# NinjaPCRf-131101.net
KiCad netlist of a schematic drawn in EAGLE
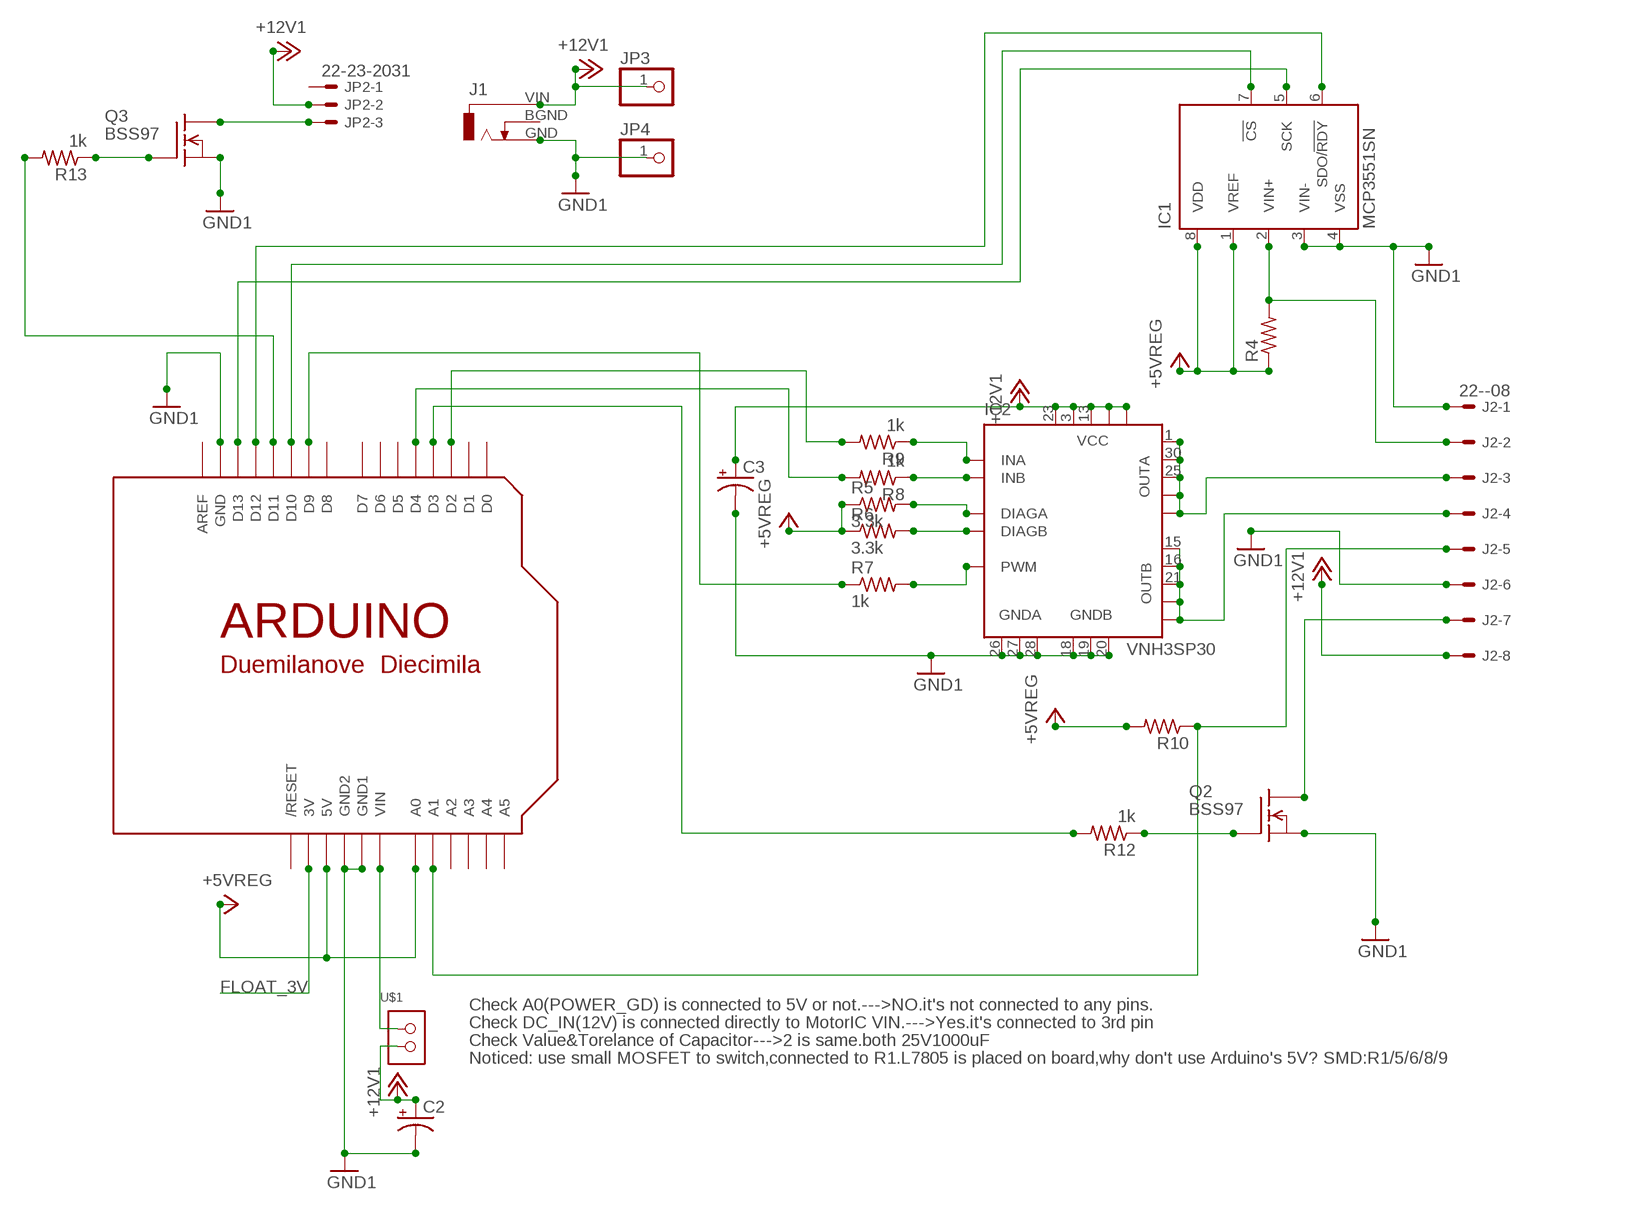
[diagram p0: schematic, sheet 1]

(export (version "E")
  (design (tool "Eeschema 10.0.6"))
  (components
    (comp (ref "C2")
      (value "CPOL-USE5-8.5")
      (footprint "eagle-import:E5-8,5")
      (libsource (lib "eagle-import") (part "CPOL-USE5-8.5"))
    )
    (comp (ref "C3")
      (value "CPOL-USE5-13")
      (footprint "eagle-import:E5-13")
      (libsource (lib "eagle-import") (part "CPOL-USE5-13"))
    )
    (comp (ref "IC1")
      (value "MCP3551SN")
      (footprint "eagle-import:SO-08")
      (fields (field (name "MPN") "MCP3551-E/SN"))
      (libsource (lib "eagle-import") (part "MCP355SN1"))
    )
    (comp (ref "IC2")
      (value "VNH3SP30")
      (footprint "eagle-import:MULTIPOWERSO-30")
      (fields (field (name "MPN") "VNH3SP30-E"))
      (libsource (lib "eagle-import") (part "VNH3SP30"))
    )
    (comp (ref "J1")
      (value "DCJ0303")
      (footprint "eagle-import:DCJ0303")
      (libsource (lib "eagle-import") (part "DCJ0303"))
    )
    (comp (ref "J2")
      (value "22--08")
      (footprint "eagle-import:POLOLU-8-VERTICAL")
      (libsource (lib "eagle-import") (part "22-?-08"))
    )
    (comp (ref "JP2")
      (value "22-23-2031")
      (footprint "eagle-import:22-23-2031")
      (fields (field (name "MF") "MOLEX"))
      (libsource (lib "eagle-import") (part "22-23-2031"))
    )
    (comp (ref "JP3")
      (value "PINHD-1X1")
      (footprint "eagle-import:1X01")
      (libsource (lib "eagle-import") (part "PINHD-1X1"))
    )
    (comp (ref "JP4")
      (value "PINHD-1X1")
      (footprint "eagle-import:1X01")
      (libsource (lib "eagle-import") (part "PINHD-1X1"))
    )
    (comp (ref "Q2")
      (value "BSS97")
      (footprint "eagle-import:TO202")
      (libsource (lib "eagle-import") (part "BSS97"))
    )
    (comp (ref "Q3")
      (value "BSS97")
      (footprint "eagle-import:TO202")
      (libsource (lib "eagle-import") (part "BSS97"))
    )
    (comp (ref "R4")
      (value "R-US_R0603")
      (footprint "eagle-import:R0603")
      (libsource (lib "eagle-import") (part "resistor_R-US_R0603"))
    )
    (comp (ref "R5")
      (value "3.3k")
      (footprint "eagle-import:R0603")
      (libsource (lib "eagle-import") (part "R-US_R0603"))
    )
    (comp (ref "R6")
      (value "3.3k")
      (footprint "eagle-import:R0603")
      (libsource (lib "eagle-import") (part "R-US_R0603"))
    )
    (comp (ref "R7")
      (value "1k")
      (footprint "eagle-import:R0603")
      (libsource (lib "eagle-import") (part "R-US_R0603"))
    )
    (comp (ref "R8")
      (value "1k")
      (footprint "eagle-import:R0603")
      (libsource (lib "eagle-import") (part "R-US_R0603"))
    )
    (comp (ref "R9")
      (value "1k")
      (footprint "eagle-import:R0603")
      (libsource (lib "eagle-import") (part "R-US_R0603"))
    )
    (comp (ref "R10")
      (value "R-US_R0603")
      (footprint "eagle-import:R0603")
      (libsource (lib "eagle-import") (part "resistor_R-US_R0603"))
    )
    (comp (ref "R12")
      (value "1k")
      (footprint "eagle-import:R0603")
      (libsource (lib "eagle-import") (part "resistor_R-US_R0603"))
    )
    (comp (ref "R13")
      (value "1k")
      (footprint "eagle-import:R0603")
      (libsource (lib "eagle-import") (part "resistor_R-US_R0603"))
    )
    (comp (ref "U$1")
      (value "1X02")
      (footprint "eagle-import:1X02_1.1_UNSIGNED")
      (libsource (lib "eagle-import") (part "1X02"))
    )
    (comp (ref "U$3")
      (value "ARDUINONS")
      (footprint "eagle-import:ARDUINO-NOSILK")
      (libsource (lib "eagle-import") (part "ARDUINONS"))
    )
  )
  (nets
    (net (code "1") (name "+5VREG") (class "Default")
      (node (ref "IC1") (pin "1") (pinfunction "VREF_1") (pintype "input"))
      (node (ref "IC1") (pin "8") (pinfunction "VDD_8") (pintype "power_in"))
      (node (ref "R10") (pin "2") (pinfunction "2_2") (pintype "passive"))
      (node (ref "R4") (pin "1") (pinfunction "1_1") (pintype "passive"))
      (node (ref "R5") (pin "1") (pinfunction "1_1") (pintype "passive"))
      (node (ref "R6") (pin "1") (pinfunction "1_1") (pintype "passive"))
      (node (ref "U$3") (pin "5V") (pinfunction "5V_5V") (pintype "power_in"))
      (node (ref "U$3") (pin "A0") (pinfunction "A0_A0") (pintype "bidirectional"))
    )
    (net (code "2") (name "+12V1") (class "Default")
      (node (ref "C2") (pin "+") (pinfunction "+_+") (pintype "passive"))
      (node (ref "C3") (pin "+") (pinfunction "+_+") (pintype "passive"))
      (node (ref "IC2") (pin "13") (pinfunction "VCC_13") (pintype "power_in"))
      (node (ref "IC2") (pin "23") (pinfunction "VCC_23") (pintype "power_in"))
      (node (ref "IC2") (pin "3") (pinfunction "VCC_3") (pintype "power_in"))
      (node (ref "IC2") (pin "VCC") (pinfunction "VCC_VCC") (pintype "power_in"))
      (node (ref "IC2") (pin "VCC@1") (pinfunction "VCC_VCC@1") (pintype "power_in"))
      (node (ref "J1") (pin "VIN") (pinfunction "VIN_VIN") (pintype "passive"))
      (node (ref "J2") (pin "8") (pinfunction "S_8") (pintype "passive"))
      (node (ref "JP2") (pin "2") (pinfunction "S_2") (pintype "passive"))
      (node (ref "JP3") (pin "1") (pinfunction "1_1") (pintype "passive"))
      (node (ref "U$1") (pin "2") (pinfunction "2_2") (pintype "passive"))
    )
    (net (code "3") (name "/FLOAT_3V") (class "Default")
      (node (ref "U$3") (pin "3V") (pinfunction "3V_3V") (pintype "power_in"))
    )
    (net (code "4") (name "GND1") (class "Default")
      (node (ref "C2") (pin "-") (pinfunction "-_-") (pintype "passive"))
      (node (ref "C3") (pin "-") (pinfunction "-_-") (pintype "passive"))
      (node (ref "IC1") (pin "3") (pinfunction "VIN-_3") (pintype "input"))
      (node (ref "IC1") (pin "4") (pinfunction "VSS_4") (pintype "power_in"))
      (node (ref "IC2") (pin "18") (pinfunction "GNDB_18") (pintype "power_in"))
      (node (ref "IC2") (pin "19") (pinfunction "GNDB_19") (pintype "power_in"))
      (node (ref "IC2") (pin "20") (pinfunction "GNDB_20") (pintype "power_in"))
      (node (ref "IC2") (pin "26") (pinfunction "GNDA_26") (pintype "power_in"))
      (node (ref "IC2") (pin "27") (pinfunction "GNDA_27") (pintype "power_in"))
      (node (ref "IC2") (pin "28") (pinfunction "GNDA_28") (pintype "power_in"))
      (node (ref "J1") (pin "GND") (pinfunction "GND_GND") (pintype "passive"))
      (node (ref "J2") (pin "1") (pinfunction "S_1") (pintype "passive"))
      (node (ref "J2") (pin "6") (pinfunction "S_6") (pintype "passive"))
      (node (ref "JP4") (pin "1") (pinfunction "1_1") (pintype "passive"))
      (node (ref "Q2") (pin "1") (pinfunction "S_1") (pintype "passive"))
      (node (ref "Q3") (pin "1") (pinfunction "S_1") (pintype "passive"))
      (node (ref "U$3") (pin "GND") (pinfunction "GND_GND") (pintype "power_in"))
      (node (ref "U$3") (pin "GND1") (pinfunction "GND1_GND1") (pintype "power_in"))
      (node (ref "U$3") (pin "GND2") (pinfunction "GND2_GND2") (pintype "power_in"))
    )
    (net (code "5") (name "Net-(IC1-SCK)") (class "Default")
      (node (ref "IC1") (pin "5") (pinfunction "SCK_5") (pintype "input"))
      (node (ref "U$3") (pin "D13") (pinfunction "D13_D13") (pintype "bidirectional"))
    )
    (net (code "6") (name "Net-(IC1-SDO{slash}~{RDY})") (class "Default")
      (node (ref "IC1") (pin "6") (pinfunction "SDO/~{RDY}_6") (pintype "output"))
      (node (ref "U$3") (pin "D12") (pinfunction "D12_D12") (pintype "bidirectional"))
    )
    (net (code "7") (name "Net-(IC1-VIN+)") (class "Default")
      (node (ref "IC1") (pin "2") (pinfunction "VIN+_2") (pintype "input"))
      (node (ref "J2") (pin "2") (pinfunction "S_2") (pintype "passive"))
      (node (ref "R4") (pin "2") (pinfunction "2_2") (pintype "passive"))
    )
    (net (code "8") (name "Net-(IC1-~{CS})") (class "Default")
      (node (ref "IC1") (pin "7") (pinfunction "~{CS}_7") (pintype "input"))
      (node (ref "U$3") (pin "D10") (pinfunction "D10_D10") (pintype "bidirectional"))
    )
    (net (code "9") (name "Net-(IC2-DIAGA)") (class "Default")
      (node (ref "IC2") (pin "6") (pinfunction "DIAGA_6") (pintype "open_collector"))
      (node (ref "R5") (pin "2") (pinfunction "2_2") (pintype "passive"))
    )
    (net (code "10") (name "Net-(IC2-DIAGB)") (class "Default")
      (node (ref "IC2") (pin "10") (pinfunction "DIAGB_10") (pintype "open_collector"))
      (node (ref "R6") (pin "2") (pinfunction "2_2") (pintype "passive"))
    )
    (net (code "11") (name "Net-(IC2-INA)") (class "Default")
      (node (ref "IC2") (pin "5") (pinfunction "INA_5") (pintype "input"))
      (node (ref "R9") (pin "1") (pinfunction "1_1") (pintype "passive"))
    )
    (net (code "12") (name "Net-(IC2-INB)") (class "Default")
      (node (ref "IC2") (pin "11") (pinfunction "INB_11") (pintype "input"))
      (node (ref "R8") (pin "1") (pinfunction "1_1") (pintype "passive"))
    )
    (net (code "13") (name "Net-(IC2-PWM)") (class "Default")
      (node (ref "IC2") (pin "8") (pinfunction "PWM_8") (pintype "input"))
      (node (ref "R7") (pin "2") (pinfunction "2_2") (pintype "passive"))
    )
    (net (code "14") (name "Net-(J2C-S)") (class "Default")
      (node (ref "IC2") (pin "1") (pinfunction "OUTA_1") (pintype "output"))
      (node (ref "IC2") (pin "25") (pinfunction "OUTA_25") (pintype "passive"))
      (node (ref "IC2") (pin "30") (pinfunction "OUTA_30") (pintype "passive"))
      (node (ref "IC2") (pin "OUTA") (pinfunction "OUTA_OUTA") (pintype "passive"))
      (node (ref "IC2") (pin "OUTA@1") (pinfunction "OUTA_OUTA@1") (pintype "passive"))
      (node (ref "J2") (pin "3") (pinfunction "S_3") (pintype "passive"))
    )
    (net (code "15") (name "Net-(J2D-S)") (class "Default")
      (node (ref "IC2") (pin "15") (pinfunction "OUTB_15") (pintype "output"))
      (node (ref "IC2") (pin "16") (pinfunction "OUTB_16") (pintype "passive"))
      (node (ref "IC2") (pin "21") (pinfunction "OUTB_21") (pintype "passive"))
      (node (ref "IC2") (pin "OUTB") (pinfunction "OUTB_OUTB") (pintype "passive"))
      (node (ref "IC2") (pin "OUTB@1") (pinfunction "OUTB_OUTB@1") (pintype "passive"))
      (node (ref "J2") (pin "4") (pinfunction "S_4") (pintype "passive"))
    )
    (net (code "16") (name "Net-(J2E-S)") (class "Default")
      (node (ref "J2") (pin "5") (pinfunction "S_5") (pintype "passive"))
      (node (ref "R10") (pin "1") (pinfunction "1_1") (pintype "passive"))
      (node (ref "U$3") (pin "A1") (pinfunction "A1_A1") (pintype "bidirectional"))
    )
    (net (code "17") (name "Net-(J2G-S)") (class "Default")
      (node (ref "J2") (pin "7") (pinfunction "S_7") (pintype "passive"))
      (node (ref "Q2") (pin "2") (pinfunction "D_2") (pintype "passive"))
    )
    (net (code "18") (name "Net-(JP2C-S)") (class "Default")
      (node (ref "JP2") (pin "3") (pinfunction "S_3") (pintype "passive"))
      (node (ref "Q3") (pin "2") (pinfunction "D_2") (pintype "passive"))
    )
    (net (code "19") (name "Net-(Q2-G)") (class "Default")
      (node (ref "Q2") (pin "3") (pinfunction "G_3") (pintype "passive"))
      (node (ref "R12") (pin "1") (pinfunction "1_1") (pintype "passive"))
    )
    (net (code "20") (name "Net-(Q3-G)") (class "Default")
      (node (ref "Q3") (pin "3") (pinfunction "G_3") (pintype "passive"))
      (node (ref "R13") (pin "1") (pinfunction "1_1") (pintype "passive"))
    )
    (net (code "21") (name "Net-(R7-Pad1)") (class "Default")
      (node (ref "R7") (pin "1") (pinfunction "1_1") (pintype "passive"))
      (node (ref "U$3") (pin "D9") (pinfunction "D9_D9") (pintype "bidirectional"))
    )
    (net (code "22") (name "Net-(R8-Pad2)") (class "Default")
      (node (ref "R8") (pin "2") (pinfunction "2_2") (pintype "passive"))
      (node (ref "U$3") (pin "D4") (pinfunction "D4_D4") (pintype "bidirectional"))
    )
    (net (code "23") (name "Net-(R9-Pad2)") (class "Default")
      (node (ref "R9") (pin "2") (pinfunction "2_2") (pintype "passive"))
      (node (ref "U$3") (pin "D2") (pinfunction "D2_D2") (pintype "bidirectional"))
    )
    (net (code "24") (name "Net-(R12-Pad2)") (class "Default")
      (node (ref "R12") (pin "2") (pinfunction "2_2") (pintype "passive"))
      (node (ref "U$3") (pin "D3") (pinfunction "D3_D3") (pintype "bidirectional"))
    )
    (net (code "25") (name "Net-(R13-Pad2)") (class "Default")
      (node (ref "R13") (pin "2") (pinfunction "2_2") (pintype "passive"))
      (node (ref "U$3") (pin "D11") (pinfunction "D11_D11") (pintype "bidirectional"))
    )
    (net (code "26") (name "Net-(U$1-Pad1)") (class "Default")
      (node (ref "U$1") (pin "1") (pinfunction "1_1") (pintype "passive"))
      (node (ref "U$3") (pin "VIN") (pinfunction "VIN_VIN") (pintype "power_in"))
    )
    (net (code "27") (name "unconnected-(J1-PadBGND)") (class "Default")
      (node (ref "J1") (pin "BGND") (pinfunction "BGND_BGND") (pintype "passive"))
    )
    (net (code "28") (name "unconnected-(JP2A-S-Pad1)") (class "Default")
      (node (ref "JP2") (pin "1") (pinfunction "S_1") (pintype "passive"))
    )
    (net (code "29") (name "unconnected-(U$3-PadA2)") (class "Default")
      (node (ref "U$3") (pin "A2") (pinfunction "A2_A2") (pintype "bidirectional"))
    )
    (net (code "30") (name "unconnected-(U$3-PadA3)") (class "Default")
      (node (ref "U$3") (pin "A3") (pinfunction "A3_A3") (pintype "bidirectional"))
    )
    (net (code "31") (name "unconnected-(U$3-PadA4)") (class "Default")
      (node (ref "U$3") (pin "A4") (pinfunction "A4_A4") (pintype "bidirectional"))
    )
    (net (code "32") (name "unconnected-(U$3-PadA5)") (class "Default")
      (node (ref "U$3") (pin "A5") (pinfunction "A5_A5") (pintype "bidirectional"))
    )
    (net (code "33") (name "unconnected-(U$3-PadAREF)") (class "Default")
      (node (ref "U$3") (pin "AREF") (pinfunction "AREF_AREF") (pintype "bidirectional"))
    )
    (net (code "34") (name "unconnected-(U$3-PadD0)") (class "Default")
      (node (ref "U$3") (pin "D0") (pinfunction "D0_D0") (pintype "bidirectional"))
    )
    (net (code "35") (name "unconnected-(U$3-PadD1)") (class "Default")
      (node (ref "U$3") (pin "D1") (pinfunction "D1_D1") (pintype "bidirectional"))
    )
    (net (code "36") (name "unconnected-(U$3-PadD5)") (class "Default")
      (node (ref "U$3") (pin "D5") (pinfunction "D5_D5") (pintype "bidirectional"))
    )
    (net (code "37") (name "unconnected-(U$3-PadD6)") (class "Default")
      (node (ref "U$3") (pin "D6") (pinfunction "D6_D6") (pintype "bidirectional"))
    )
    (net (code "38") (name "unconnected-(U$3-PadD7)") (class "Default")
      (node (ref "U$3") (pin "D7") (pinfunction "D7_D7") (pintype "bidirectional"))
    )
    (net (code "39") (name "unconnected-(U$3-PadD8)") (class "Default")
      (node (ref "U$3") (pin "D8") (pinfunction "D8_D8") (pintype "bidirectional"))
    )
    (net (code "40") (name "unconnected-(U$3-{slash}RESET-PadRESET)") (class "Default")
      (node (ref "U$3") (pin "RESET") (pinfunction "/RESET_RESET") (pintype "bidirectional"))
    )
  )
)
